# IPMC_MACP.net
KiCad netlist of a schematic drawn in Altium Designer
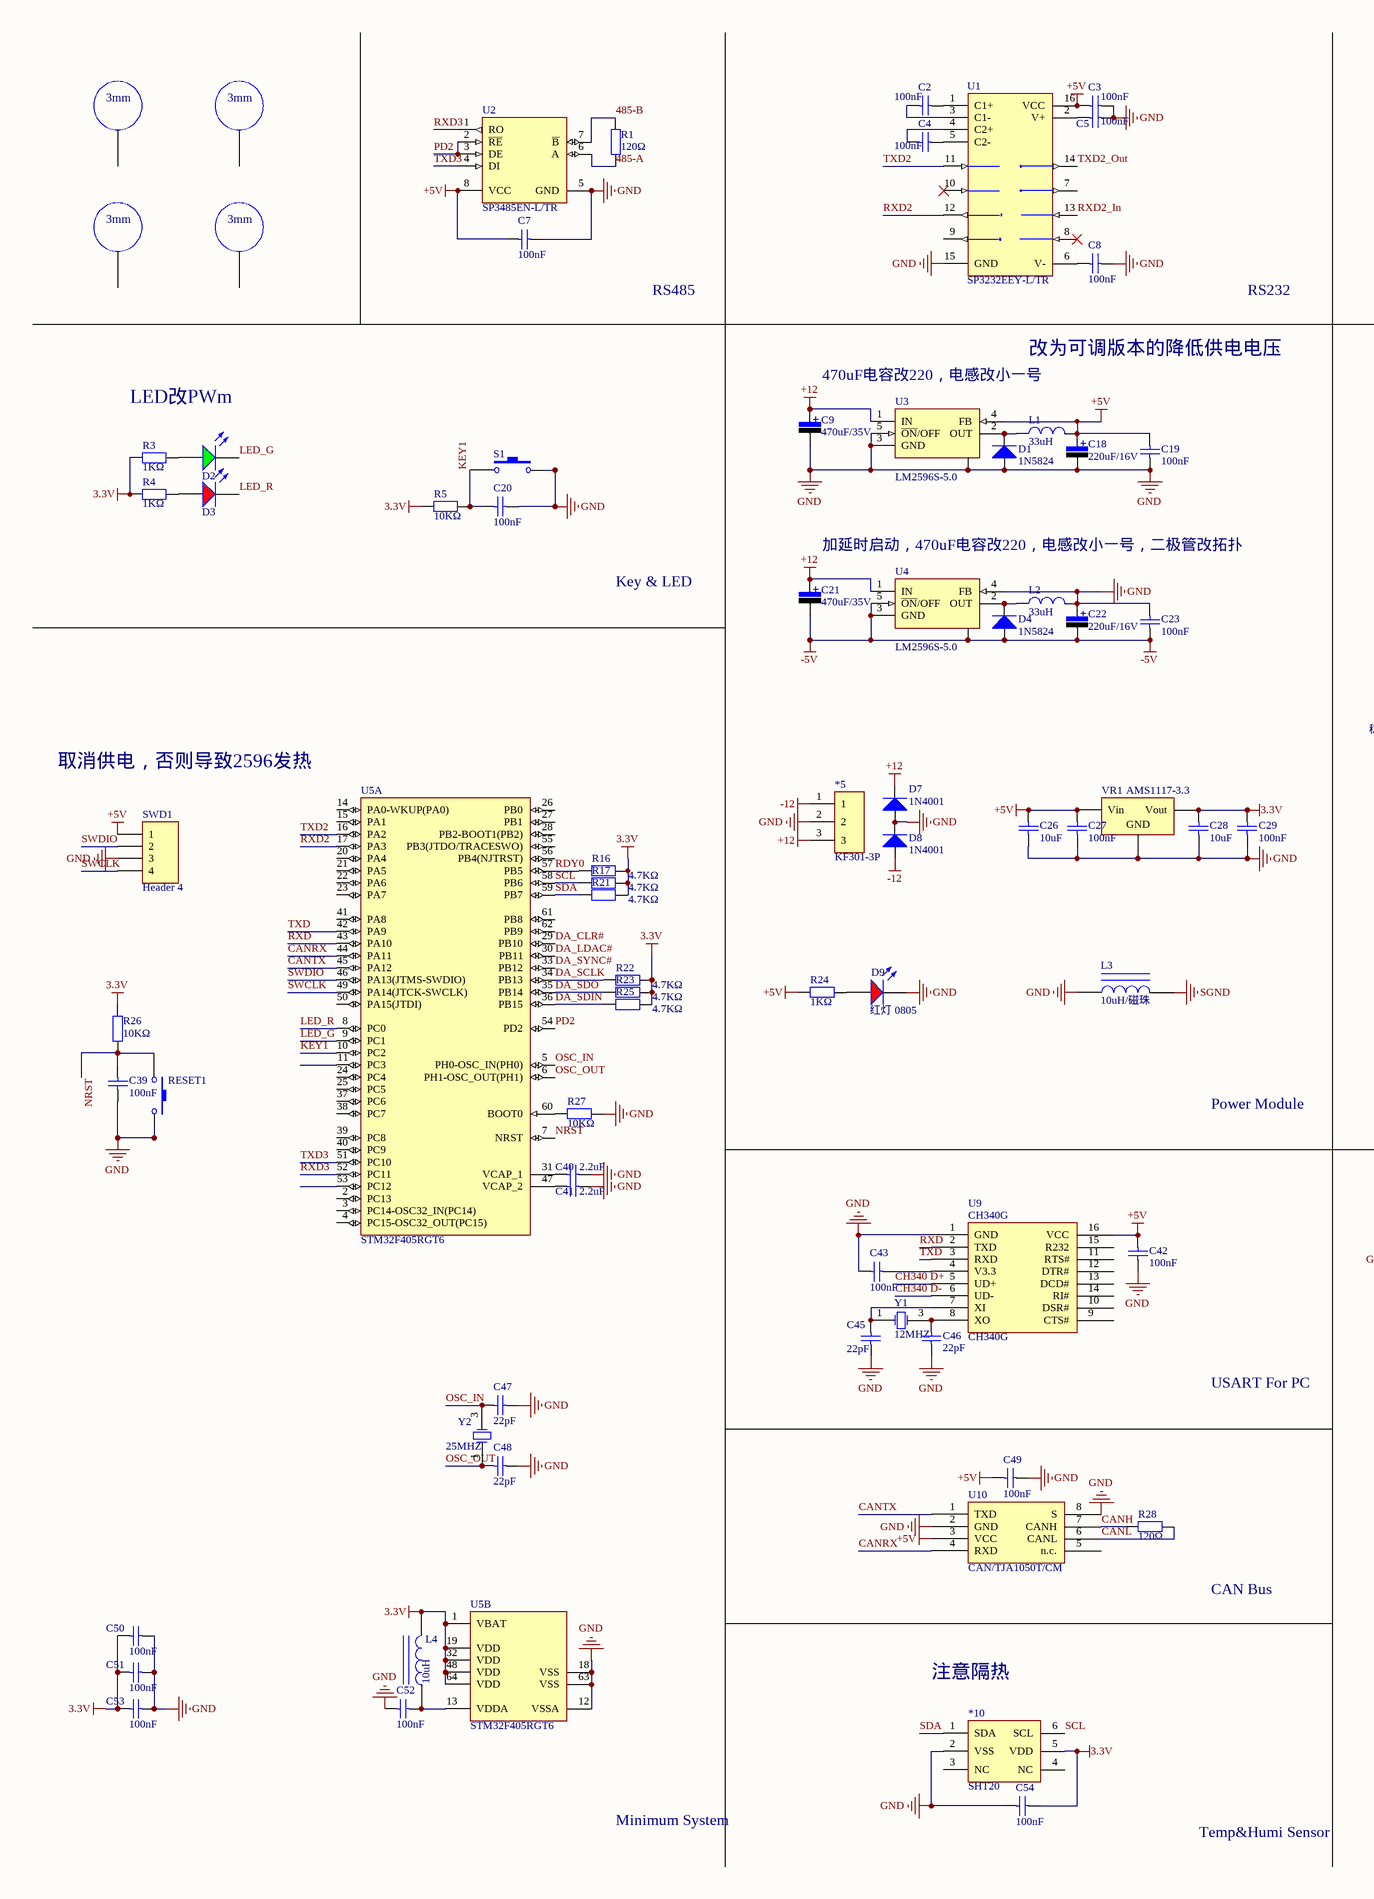
[diagram p0: IPMC_MACP.SchDoc, left]
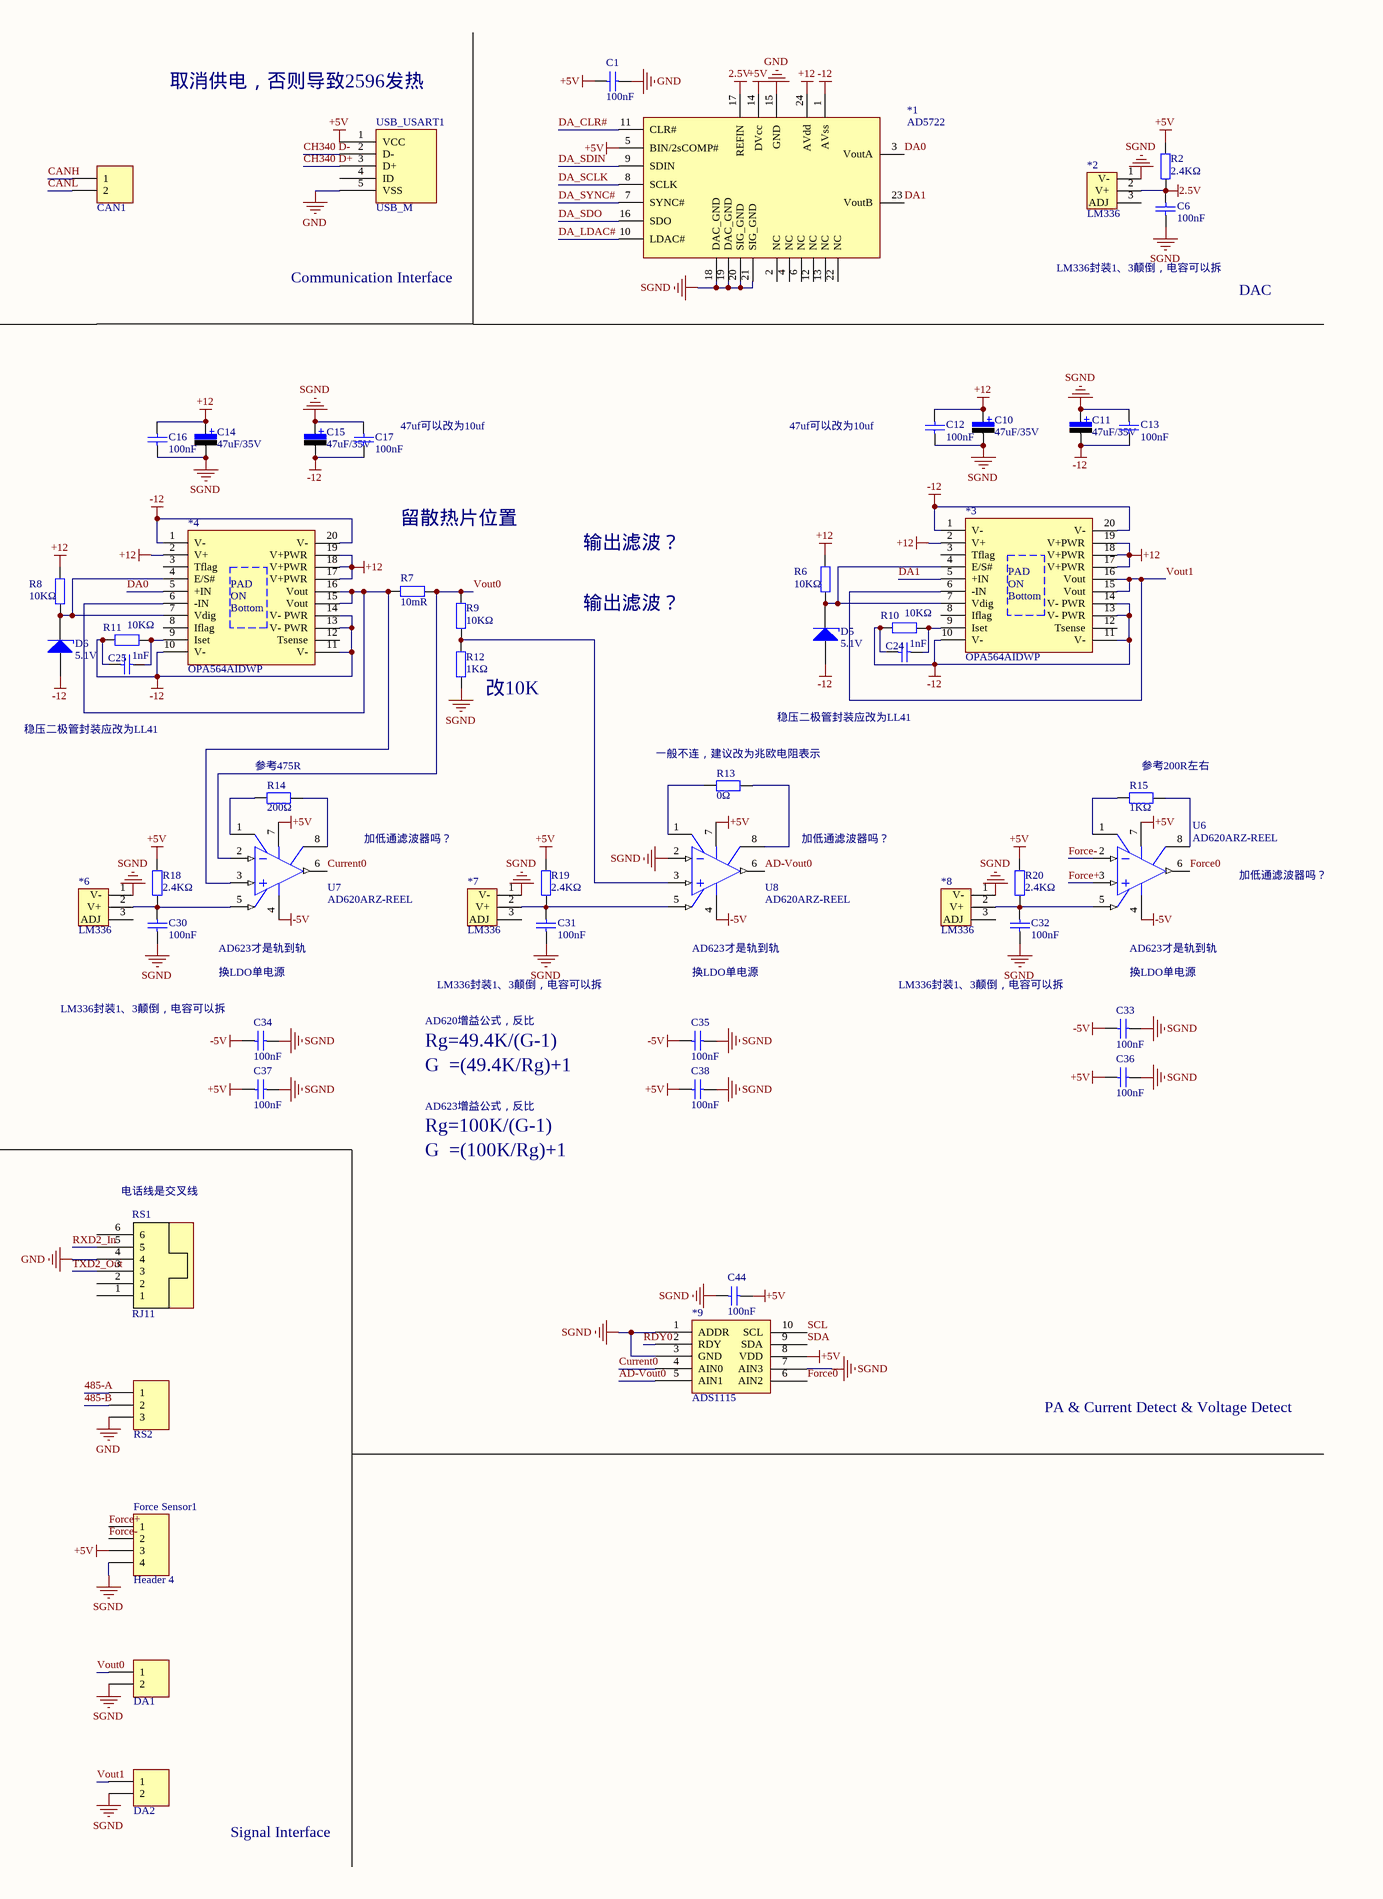
[diagram p1: IPMC_MACP.SchDoc, right]

(export (version "E")
  (design (tool "Eeschema 10.0.6"))
  (components
    (comp (ref "*1")
      (value "AD5722")
      (footprint "TSSOP24P")
      (description "双极性DAC")
      (libsource (lib "fszhang") (part "AD5722"))
    )
    (comp (ref "*2")
      (value "LM336")
      (footprint "TO-92A")
      (description "基准电压芯片2.5/5V")
      (libsource (lib "fszhang") (part "LM336"))
    )
    (comp (ref "*3")
      (value "OPA564AIDWP")
      (footprint "HSOP20")
      (description "PAD on Bottom")
      (libsource (lib "fszhang") (part "OPA564AIDWP"))
    )
    (comp (ref "*4")
      (value "OPA564AIDWP")
      (footprint "HSOP20")
      (description "PAD on Bottom")
      (libsource (lib "fszhang") (part "OPA564AIDWP"))
    )
    (comp (ref "*5")
      (value "KF301-3P")
      (footprint "KF301-3P")
      (description "蓝色端子")
      (libsource (lib "fszhang") (part "KF301-3P"))
    )
    (comp (ref "*6")
      (value "LM336")
      (footprint "TO-92A")
      (description "基准电压芯片2.5/5V")
      (libsource (lib "fszhang") (part "LM336"))
    )
    (comp (ref "*7")
      (value "LM336")
      (footprint "TO-92A")
      (description "基准电压芯片2.5/5V")
      (libsource (lib "fszhang") (part "LM336"))
    )
    (comp (ref "*8")
      (value "LM336")
      (footprint "TO-92A")
      (description "基准电压芯片2.5/5V")
      (libsource (lib "fszhang") (part "LM336"))
    )
    (comp (ref "*9") (value "ADS1115") (footprint "MSOP-UN10_N") (libsource (lib "fszhang") (part "ADS1115")))
    (comp (ref "*10") (value "SHT20") (footprint "DFN6") (libsource (lib "fszhang") (part "SHT20")))
    (comp (ref "C1")
      (value "100nF")
      (footprint "0805_C")
      (description "贴片电容")
      (libsource (lib "Miscellaneous Devices LC") (part "0805 100nF(104) 10% 50V"))
    )
    (comp (ref "C2")
      (value "100nF")
      (footprint "0805_C")
      (description "贴片电容")
      (libsource (lib "Miscellaneous Devices LC") (part "0805 100nF(104) 10% 50V"))
    )
    (comp (ref "C3")
      (value "100nF")
      (footprint "0805_C")
      (description "贴片电容")
      (libsource (lib "Miscellaneous Devices LC") (part "0805 100nF(104) 10% 50V"))
    )
    (comp (ref "C4")
      (value "100nF")
      (footprint "0805_C")
      (description "贴片电容")
      (libsource (lib "Miscellaneous Devices LC") (part "0805 100nF(104) 10% 50V"))
    )
    (comp (ref "C5")
      (value "100nF")
      (footprint "0805_C")
      (description "贴片电容")
      (libsource (lib "Miscellaneous Devices LC") (part "0805 100nF(104) 10% 50V"))
    )
    (comp (ref "C6")
      (value "100nF")
      (footprint "0805_C")
      (description "贴片电容")
      (libsource (lib "Miscellaneous Devices LC") (part "0805 100nF(104) 10% 50V"))
    )
    (comp (ref "C7")
      (value "100nF")
      (footprint "0805_C")
      (description "贴片电容")
      (libsource (lib "Miscellaneous Devices LC") (part "0805 100nF(104) 10% 50V"))
    )
    (comp (ref "C8")
      (value "100nF")
      (footprint "0805_C")
      (description "贴片电容")
      (libsource (lib "Miscellaneous Devices LC") (part "0805 100nF(104) 10% 50V"))
    )
    (comp (ref "C9")
      (value "470uF/35V")
      (footprint "C-RB-S10")
      (description "极性电解电容")
      (fields (field (name "PUBLISHER") "Altium Limited"))
      (libsource (lib "fszhang") (part "Cap Pol"))
    )
    (comp (ref "C10")
      (value "47uF/35V")
      (footprint "C-RB-S6")
      (description "极性电解电容")
      (fields (field (name "PUBLISHER") "Altium Limited"))
      (libsource (lib "fszhang") (part "Cap Pol"))
    )
    (comp (ref "C11")
      (value "47uF/35V")
      (footprint "C-RB-S6")
      (description "极性电解电容")
      (fields (field (name "PUBLISHER") "Altium Limited"))
      (libsource (lib "fszhang") (part "Cap Pol"))
    )
    (comp (ref "C12")
      (value "100nF")
      (footprint "0805_C")
      (description "贴片电容")
      (libsource (lib "Miscellaneous Devices LC") (part "0805 100nF(104) 10% 50V"))
    )
    (comp (ref "C13")
      (value "100nF")
      (footprint "0805_C")
      (description "贴片电容")
      (libsource (lib "Miscellaneous Devices LC") (part "0805 100nF(104) 10% 50V"))
    )
    (comp (ref "C14")
      (value "47uF/35V")
      (footprint "C-RB-S6")
      (description "极性电解电容")
      (fields (field (name "PUBLISHER") "Altium Limited"))
      (libsource (lib "fszhang") (part "Cap Pol"))
    )
    (comp (ref "C15")
      (value "47uF/35V")
      (footprint "C-RB-S6")
      (description "极性电解电容")
      (fields (field (name "PUBLISHER") "Altium Limited"))
      (libsource (lib "fszhang") (part "Cap Pol"))
    )
    (comp (ref "C16")
      (value "100nF")
      (footprint "0805_C")
      (description "贴片电容")
      (libsource (lib "Miscellaneous Devices LC") (part "0805 100nF(104) 10% 50V"))
    )
    (comp (ref "C17")
      (value "100nF")
      (footprint "0805_C")
      (description "贴片电容")
      (libsource (lib "Miscellaneous Devices LC") (part "0805 100nF(104) 10% 50V"))
    )
    (comp (ref "C18")
      (value "220uF/16V")
      (footprint "C-RB-S6")
      (description "极性电解电容")
      (fields (field (name "PUBLISHER") "Altium Limited"))
      (libsource (lib "fszhang") (part "Cap Pol"))
    )
    (comp (ref "C19")
      (value "100nF")
      (footprint "0805_C")
      (description "贴片电容")
      (libsource (lib "Miscellaneous Devices LC") (part "0805 100nF(104) 10% 50V"))
    )
    (comp (ref "C20")
      (value "100nF")
      (footprint "0805_C")
      (description "贴片电容")
      (libsource (lib "Miscellaneous Devices LC") (part "0805 100nF(104) 10% 50V"))
    )
    (comp (ref "C21")
      (value "470uF/35V")
      (footprint "C-RB-S10")
      (description "极性电解电容")
      (fields (field (name "PUBLISHER") "Altium Limited"))
      (libsource (lib "fszhang") (part "Cap Pol"))
    )
    (comp (ref "C22")
      (value "220uF/16V")
      (footprint "C-RB-S6")
      (description "极性电解电容")
      (fields (field (name "PUBLISHER") "Altium Limited"))
      (libsource (lib "fszhang") (part "Cap Pol"))
    )
    (comp (ref "C23")
      (value "100nF")
      (footprint "0805_C")
      (description "贴片电容")
      (libsource (lib "Miscellaneous Devices LC") (part "0805 100nF(104) 10% 50V"))
    )
    (comp (ref "C24")
      (value "1nF")
      (footprint "0805_C")
      (description "贴片电容")
      (libsource (lib "Miscellaneous Devices LC") (part "0805 1nF (102) 10% 50V"))
    )
    (comp (ref "C25")
      (value "1nF")
      (footprint "0805_C")
      (description "贴片电容")
      (libsource (lib "Miscellaneous Devices LC") (part "0805 1nF (102) 10% 50V"))
    )
    (comp (ref "C26")
      (value "10uF")
      (footprint "0805_C")
      (description "贴片电容")
      (libsource (lib "Miscellaneous Devices LC") (part "0805 10uF (106) 10% 25V"))
    )
    (comp (ref "C27")
      (value "100nF")
      (footprint "0805_C")
      (description "贴片电容")
      (libsource (lib "Miscellaneous Devices LC") (part "0805 100nF(104) 10% 50V"))
    )
    (comp (ref "C28")
      (value "10uF")
      (footprint "0805_C")
      (description "贴片电容")
      (libsource (lib "Miscellaneous Devices LC") (part "0805 10uF (106) 10% 25V"))
    )
    (comp (ref "C29")
      (value "100nF")
      (footprint "0805_C")
      (description "贴片电容")
      (libsource (lib "Miscellaneous Devices LC") (part "0805 100nF(104) 10% 50V"))
    )
    (comp (ref "C30")
      (value "100nF")
      (footprint "0805_C")
      (description "贴片电容")
      (libsource (lib "Miscellaneous Devices LC") (part "0805 100nF(104) 10% 50V"))
    )
    (comp (ref "C31")
      (value "100nF")
      (footprint "0805_C")
      (description "贴片电容")
      (libsource (lib "Miscellaneous Devices LC") (part "0805 100nF(104) 10% 50V"))
    )
    (comp (ref "C32")
      (value "100nF")
      (footprint "0805_C")
      (description "贴片电容")
      (libsource (lib "Miscellaneous Devices LC") (part "0805 100nF(104) 10% 50V"))
    )
    (comp (ref "C33")
      (value "100nF")
      (footprint "0805_C")
      (description "贴片电容")
      (libsource (lib "Miscellaneous Devices LC") (part "0805 100nF(104) 10% 50V"))
    )
    (comp (ref "C34")
      (value "100nF")
      (footprint "0805_C")
      (description "贴片电容")
      (libsource (lib "Miscellaneous Devices LC") (part "0805 100nF(104) 10% 50V"))
    )
    (comp (ref "C35")
      (value "100nF")
      (footprint "0805_C")
      (description "贴片电容")
      (libsource (lib "Miscellaneous Devices LC") (part "0805 100nF(104) 10% 50V"))
    )
    (comp (ref "C36")
      (value "100nF")
      (footprint "0805_C")
      (description "贴片电容")
      (libsource (lib "Miscellaneous Devices LC") (part "0805 100nF(104) 10% 50V"))
    )
    (comp (ref "C37")
      (value "100nF")
      (footprint "0805_C")
      (description "贴片电容")
      (libsource (lib "Miscellaneous Devices LC") (part "0805 100nF(104) 10% 50V"))
    )
    (comp (ref "C38")
      (value "100nF")
      (footprint "0805_C")
      (description "贴片电容")
      (libsource (lib "Miscellaneous Devices LC") (part "0805 100nF(104) 10% 50V"))
    )
    (comp (ref "C39")
      (value "100nF")
      (footprint "0805_C")
      (description "贴片电容")
      (libsource (lib "Miscellaneous Devices LC") (part "0805 100nF(104) 10% 50V"))
    )
    (comp (ref "C40")
      (value "2.2uF")
      (footprint "0805_C")
      (description "贴片电容")
      (libsource (lib "Miscellaneous Devices LC") (part "0805 2.2uF (225) 20% 50V"))
    )
    (comp (ref "C41")
      (value "2.2uF")
      (footprint "0805_C")
      (description "贴片电容")
      (libsource (lib "Miscellaneous Devices LC") (part "0805 2.2uF (225) 20% 50V"))
    )
    (comp (ref "C42")
      (value "100nF")
      (footprint "0805_C")
      (description "贴片电容")
      (libsource (lib "Miscellaneous Devices LC") (part "0805 100nF(104) 10% 50V"))
    )
    (comp (ref "C43")
      (value "100nF")
      (footprint "0805_C")
      (description "贴片电容")
      (libsource (lib "Miscellaneous Devices LC") (part "0805 100nF(104) 10% 50V"))
    )
    (comp (ref "C44")
      (value "100nF")
      (footprint "0805_C")
      (description "贴片电容")
      (libsource (lib "Miscellaneous Devices LC") (part "0805 100nF(104) 10% 50V"))
    )
    (comp (ref "C45")
      (value "22pF")
      (footprint "0805_C")
      (description "贴片电容")
      (libsource (lib "Miscellaneous Devices LC") (part "0805 22pF (220) 5% 50V"))
    )
    (comp (ref "C46")
      (value "22pF")
      (footprint "0805_C")
      (description "贴片电容")
      (libsource (lib "Miscellaneous Devices LC") (part "0805 22pF (220) 5% 50V"))
    )
    (comp (ref "C47")
      (value "22pF")
      (footprint "0805_C")
      (description "贴片电容")
      (libsource (lib "Miscellaneous Devices LC") (part "0805 22pF (220) 5% 50V"))
    )
    (comp (ref "C48")
      (value "22pF")
      (footprint "0805_C")
      (description "贴片电容")
      (libsource (lib "Miscellaneous Devices LC") (part "0805 22pF (220) 5% 50V"))
    )
    (comp (ref "C49")
      (value "100nF")
      (footprint "0805_C")
      (description "贴片电容")
      (libsource (lib "Miscellaneous Devices LC") (part "0805 100nF(104) 10% 50V"))
    )
    (comp (ref "C50")
      (value "100nF")
      (footprint "0805_C")
      (description "贴片电容")
      (libsource (lib "Miscellaneous Devices LC") (part "0805 100nF(104) 10% 50V"))
    )
    (comp (ref "C51")
      (value "100nF")
      (footprint "0805_C")
      (description "贴片电容")
      (libsource (lib "Miscellaneous Devices LC") (part "0805 100nF(104) 10% 50V"))
    )
    (comp (ref "C52")
      (value "100nF")
      (footprint "0805_C")
      (description "贴片电容")
      (libsource (lib "Miscellaneous Devices LC") (part "0805 100nF(104) 10% 50V"))
    )
    (comp (ref "C53")
      (value "100nF")
      (footprint "0805_C")
      (description "贴片电容")
      (libsource (lib "Miscellaneous Devices LC") (part "0805 100nF(104) 10% 50V"))
    )
    (comp (ref "C54")
      (value "100nF")
      (footprint "0805_C")
      (description "贴片电容")
      (libsource (lib "Miscellaneous Devices LC") (part "0805 100nF(104) 10% 50V"))
    )
    (comp (ref "CAN1")
      (value "Header 2")
      (footprint "HDR2X1_B1")
      (description "接插件")
      (fields (field (name "PUBLISHER") "Altium Limited"))
      (libsource (lib "fszhang") (part "Header 2"))
    )
    (comp (ref "D1")
      (value "1N5824")
      (footprint "DIODE-SMA")
      (description "二极管")
      (fields (field (name "PUBLISHER") "Altium Limited"))
      (libsource (lib "fszhang") (part "Diode"))
    )
    (comp (ref "D2")
      (value "翠绿 0805")
      (footprint "0805_LED_S1")
      (description "发光二极管")
      (libsource (lib "Miscellaneous Devices LC") (part "0805 翠绿"))
    )
    (comp (ref "D3")
      (value "红灯 0805")
      (footprint "0805_LED_S1")
      (description "发光二极管")
      (libsource (lib "Miscellaneous Devices LC") (part "0805 红灯"))
    )
    (comp (ref "D4")
      (value "1N5824")
      (footprint "DIODE-SMA")
      (description "二极管")
      (fields (field (name "PUBLISHER") "Altium Limited"))
      (libsource (lib "fszhang") (part "Diode"))
    )
    (comp (ref "D5")
      (value "5.1V")
      (footprint "DIODE-1206")
      (description "稳压二极管")
      (fields (field (name "PUBLISHER") "Altium Limited"))
      (libsource (lib "fszhang") (part "Diode-Z"))
    )
    (comp (ref "D6")
      (value "5.1V")
      (footprint "DIODE-1206")
      (description "稳压二极管")
      (fields (field (name "PUBLISHER") "Altium Limited"))
      (libsource (lib "fszhang") (part "Diode-Z"))
    )
    (comp (ref "D7")
      (value "1N4001")
      (footprint "DIODE-SMA")
      (description "二极管")
      (fields (field (name "PUBLISHER") "Altium Limited"))
      (libsource (lib "fszhang") (part "Diode"))
    )
    (comp (ref "D8")
      (value "1N4001")
      (footprint "DIODE-SMA")
      (description "二极管")
      (fields (field (name "PUBLISHER") "Altium Limited"))
      (libsource (lib "fszhang") (part "Diode"))
    )
    (comp (ref "D9")
      (value "红灯 0805")
      (footprint "0805_LED_S1")
      (description "发光二极管")
      (libsource (lib "Miscellaneous Devices LC") (part "0805 红灯"))
    )
    (comp (ref "DA1")
      (value "Header 2")
      (footprint "HDR2X1_B1")
      (description "接插件")
      (fields (field (name "PUBLISHER") "Altium Limited"))
      (libsource (lib "fszhang") (part "Header 2"))
    )
    (comp (ref "DA2")
      (value "Header 2")
      (footprint "HDR2X1_B1")
      (description "接插件")
      (fields (field (name "PUBLISHER") "Altium Limited"))
      (libsource (lib "fszhang") (part "Header 2"))
    )
    (comp (ref "Force Sensor1")
      (value "Header 4")
      (footprint "fszhang:HDR4X1_B1")
      (description "Header, 4-Pin")
      (fields (field (name "PUBLISHER") "Altium Limited"))
      (libsource (lib "Miscellaneous Connectors") (part "Header 4"))
    )
    (comp (ref "L1")
      (value "33uH")
      (footprint "L-SMD-12")
      (description "电感")
      (fields (field (name "PUBLISHER") "Altium Limited"))
      (libsource (lib "fszhang") (part "Inductor"))
    )
    (comp (ref "L2")
      (value "33uH")
      (footprint "L-SMD-12")
      (description "电感")
      (fields (field (name "PUBLISHER") "Altium Limited"))
      (libsource (lib "fszhang") (part "Inductor"))
    )
    (comp (ref "L3")
      (value "10uH/磁珠")
      (footprint "0805_L")
      (description "贴片电感")
      (libsource (lib "Miscellaneous Devices LC") (part "0805 10uH 10%"))
    )
    (comp (ref "L4")
      (value "10uH")
      (footprint "0805_L")
      (description "贴片电感")
      (libsource (lib "Miscellaneous Devices LC") (part "0805 10uH 10%"))
    )
    (comp (ref "R1")
      (value "120Ω")
      (footprint "0805_R")
      (description "贴片电阻")
      (libsource (lib "") (part "0805 120Ω (1200) 1%_1"))
    )
    (comp (ref "R2")
      (value "2.4KΩ")
      (footprint "0805_R")
      (description "贴片电阻")
      (libsource (lib "Miscellaneous Devices LC") (part "0805 2.4KΩ (2401) 1%"))
    )
    (comp (ref "R3")
      (value "1KΩ")
      (footprint "0805_R")
      (description "贴片电阻")
      (libsource (lib "Miscellaneous Devices LC") (part "0805 1KΩ (1001) 1%"))
    )
    (comp (ref "R4")
      (value "1KΩ")
      (footprint "0805_R")
      (description "贴片电阻")
      (libsource (lib "Miscellaneous Devices LC") (part "0805 1KΩ (1001) 1%"))
    )
    (comp (ref "R5")
      (value "10KΩ")
      (footprint "0805_R")
      (description "贴片电阻")
      (libsource (lib "") (part "0805 10KΩ (1002) 1%_1"))
    )
    (comp (ref "R6")
      (value "10KΩ")
      (footprint "0805_R")
      (description "贴片电阻")
      (libsource (lib "Miscellaneous Devices LC") (part "0805 10KΩ (1002) 1%"))
    )
    (comp (ref "R7")
      (value "10mR")
      (footprint "2512")
      (description "贴片电阻")
      (fields (field (name "PUBLISHER") "Altium Limited"))
      (libsource (lib "fszhang") (part "Res1"))
    )
    (comp (ref "R8")
      (value "10KΩ")
      (footprint "0805_R")
      (description "贴片电阻")
      (libsource (lib "Miscellaneous Devices LC") (part "0805 10KΩ (1002) 1%"))
    )
    (comp (ref "R9")
      (value "10KΩ")
      (footprint "0805_R")
      (description "贴片电阻")
      (libsource (lib "Miscellaneous Devices LC") (part "0805 20KΩ (2002) 1%"))
    )
    (comp (ref "R10")
      (value "10KΩ")
      (footprint "0805_R")
      (description "贴片电阻")
      (libsource (lib "") (part "0805 10KΩ (1002) 1%_1"))
    )
    (comp (ref "R11")
      (value "10KΩ")
      (footprint "0805_R")
      (description "贴片电阻")
      (libsource (lib "") (part "0805 10KΩ (1002) 1%_1"))
    )
    (comp (ref "R12")
      (value "1KΩ")
      (footprint "0805_R")
      (description "贴片电阻")
      (libsource (lib "Miscellaneous Devices LC") (part "0805 20KΩ (2002) 1%"))
    )
    (comp (ref "R13")
      (value "0Ω")
      (footprint "0805_R")
      (description "贴片电阻")
      (libsource (lib "Miscellaneous Devices LC") (part "0805 0Ω (0R0) 1%"))
    )
    (comp (ref "R14")
      (value "200Ω")
      (footprint "0805_R")
      (description "贴片电阻")
      (libsource (lib "Miscellaneous Devices LC") (part "0805 200Ω (2000) 1%"))
    )
    (comp (ref "R15")
      (value "1KΩ")
      (footprint "0805_R")
      (description "贴片电阻")
      (libsource (lib "Miscellaneous Devices LC") (part "0805 1KΩ (1001) 1%"))
    )
    (comp (ref "R16")
      (value "4.7KΩ")
      (footprint "0805_R")
      (description "贴片电阻")
      (libsource (lib "Miscellaneous Devices LC") (part "0805 4.7KΩ (4701) 1%"))
    )
    (comp (ref "R17")
      (value "4.7KΩ")
      (footprint "0805_R")
      (description "贴片电阻")
      (libsource (lib "Miscellaneous Devices LC") (part "0805 4.7KΩ (4701) 1%"))
    )
    (comp (ref "R18")
      (value "2.4KΩ")
      (footprint "0805_R")
      (description "贴片电阻")
      (libsource (lib "Miscellaneous Devices LC") (part "0805 2.4KΩ (2401) 1%"))
    )
    (comp (ref "R19")
      (value "2.4KΩ")
      (footprint "0805_R")
      (description "贴片电阻")
      (libsource (lib "Miscellaneous Devices LC") (part "0805 2.4KΩ (2401) 1%"))
    )
    (comp (ref "R20")
      (value "2.4KΩ")
      (footprint "0805_R")
      (description "贴片电阻")
      (libsource (lib "Miscellaneous Devices LC") (part "0805 2.4KΩ (2401) 1%"))
    )
    (comp (ref "R21")
      (value "4.7KΩ")
      (footprint "0805_R")
      (description "贴片电阻")
      (libsource (lib "Miscellaneous Devices LC") (part "0805 4.7KΩ (4701) 1%"))
    )
    (comp (ref "R22")
      (value "4.7KΩ")
      (footprint "0805_R")
      (description "贴片电阻")
      (libsource (lib "Miscellaneous Devices LC") (part "0805 4.7KΩ (4701) 1%"))
    )
    (comp (ref "R23")
      (value "4.7KΩ")
      (footprint "0805_R")
      (description "贴片电阻")
      (libsource (lib "Miscellaneous Devices LC") (part "0805 4.7KΩ (4701) 1%"))
    )
    (comp (ref "R24")
      (value "1KΩ")
      (footprint "0805_R")
      (description "贴片电阻")
      (libsource (lib "Miscellaneous Devices LC") (part "0805 1KΩ (1001) 1%"))
    )
    (comp (ref "R25")
      (value "4.7KΩ")
      (footprint "0805_R")
      (description "贴片电阻")
      (libsource (lib "Miscellaneous Devices LC") (part "0805 4.7KΩ (4701) 1%"))
    )
    (comp (ref "R26")
      (value "10KΩ")
      (footprint "0805_R")
      (description "贴片电阻")
      (libsource (lib "") (part "0805 10KΩ (1002) 1%_3"))
    )
    (comp (ref "R27")
      (value "10KΩ")
      (footprint "0805_R")
      (description "贴片电阻")
      (libsource (lib "") (part "0805 10KΩ (1002) 1%_2"))
    )
    (comp (ref "R28")
      (value "120Ω")
      (footprint "0805_R")
      (description "贴片电阻")
      (libsource (lib "Miscellaneous Devices LC") (part "0805 120Ω (1200) 1%"))
    )
    (comp (ref "RESET1")
      (value "SW-PB")
      (footprint "SW_PB2_A1")
      (description "微动开关")
      (fields (field (name "PUBLISHER") "Altium Limited"))
      (libsource (lib "fszhang") (part "SW-PB"))
    )
    (comp (ref "RS1") (value "RJ11") (footprint "RJ6-RJ11") (libsource (lib "fszhang") (part "RJ11")))
    (comp (ref "RS2")
      (value "Header 3")
      (footprint "HDR3X1_B1")
      (description "接插件")
      (fields (field (name "PUBLISHER") "Altium Limited"))
      (libsource (lib "fszhang") (part "Header 3"))
    )
    (comp (ref "S1")
      (value "SW-PB")
      (footprint "SW_PB2_A1")
      (description "微动开关")
      (fields (field (name "PUBLISHER") "Altium Limited"))
      (libsource (lib "fszhang") (part "SW-PB"))
    )
    (comp (ref "SWD1")
      (value "Header 4")
      (footprint "HDR1X4")
      (description "Header, 4-Pin")
      (fields (field (name "PUBLISHER") "Altium Limited"))
      (libsource (lib "Miscellaneous Connectors") (part "Header 4"))
    )
    (comp (ref "T1") (value "M3铜柱螺丝孔") (footprint "螺丝孔-3mm") (libsource (lib "fszhang") (part "M3铜柱螺丝孔")))
    (comp (ref "T2") (value "M3铜柱螺丝孔") (footprint "螺丝孔-3mm") (libsource (lib "fszhang") (part "M3铜柱螺丝孔")))
    (comp (ref "T3") (value "M3铜柱螺丝孔") (footprint "螺丝孔-3mm") (libsource (lib "fszhang") (part "M3铜柱螺丝孔")))
    (comp (ref "T4") (value "M3铜柱螺丝孔") (footprint "螺丝孔-3mm") (libsource (lib "fszhang") (part "M3铜柱螺丝孔")))
    (comp (ref "U1")
      (value "SP3232EEY-L/TR")
      (footprint "TSSOP-16")
      (description "RS232")
      (libsource (lib "Miscellaneous Devices LC") (part "SP3232EEY-L/TR"))
    )
    (comp (ref "U2")
      (value "SP3485EN-L/TR")
      (footprint "SOIC-8_150mil")
      (description "RS-485/RS-422")
      (libsource (lib "Miscellaneous Devices LC") (part "SP3485EN-L/TR"))
    )
    (comp (ref "U3")
      (value "LM2596S-5.0")
      (footprint "TO-263-5")
      (description "5V稳压芯片")
      (fields (field (name "PUBLISHER") "Altium Limited"))
      (libsource (lib "fszhang") (part "LM2596S-5.0"))
    )
    (comp (ref "U4")
      (value "LM2596S-5.0")
      (footprint "TO-263-5")
      (description "5V稳压芯片")
      (fields (field (name "PUBLISHER") "Altium Limited"))
      (libsource (lib "fszhang") (part "LM2596S-5.0"))
    )
    (comp (ref "U5")
      (value "STM32F405RGT6")
      (footprint "STM-LQFP64_L")
      (fields (field (name "MANUFACTURER") "STMicroelectronics"))
      (libsource (lib "STMicroelectronics STM32 F4") (part "STM32F405RGT6"))
    )
    (comp (ref "U6")
      (value "AD620ARZ-REEL")
      (footprint "SOIC-8_150mil")
      (description "仪放")
      (libsource (lib "Miscellaneous Devices LC") (part "AD620ARZ-REEL"))
    )
    (comp (ref "U7")
      (value "AD620ARZ-REEL")
      (footprint "SOIC-8_150mil")
      (description "仪放")
      (libsource (lib "Miscellaneous Devices LC") (part "AD620ARZ-REEL"))
    )
    (comp (ref "U8")
      (value "AD620ARZ-REEL")
      (footprint "SOIC-8_150mil")
      (description "仪放")
      (libsource (lib "Miscellaneous Devices LC") (part "AD620ARZ-REEL"))
    )
    (comp (ref "U9")
      (value "CH340G")
      (footprint "SOIC-16_150mil")
      (description "USB")
      (libsource (lib "Miscellaneous Devices LC") (part "CH340G"))
    )
    (comp (ref "U10")
      (value "CAN/TJA1050T/CM")
      (footprint "SOIC-8_150mil")
      (description "CAN")
      (libsource (lib "Miscellaneous Devices LC") (part "CAN/TJA1050T/CM"))
    )
    (comp (ref "USB_USART1")
      (value "USB_M")
      (footprint "USB_MICRO")
      (description "MicroUSB接口")
      (libsource (lib "fszhang") (part "USB_M"))
    )
    (comp (ref "VR1")
      (value "AMS1117-3.3")
      (footprint "SOT-223")
      (description "低压差线性稳压(LDO)")
      (libsource (lib "Miscellaneous Devices LC") (part "SOT-223 AMS1117-3.3"))
    )
    (comp (ref "Y1")
      (value "12MHZ")
      (footprint "SMD-3225_4P")
      (description "贴片晶振")
      (libsource (lib "Miscellaneous Devices LC") (part "SMD-3225_4P  12MHZ 20PF 10PPM"))
    )
    (comp (ref "Y2")
      (value "25MHZ")
      (footprint "SMD-3225_4P")
      (description "贴片晶振")
      (libsource (lib "Miscellaneous Devices LC") (part "SMD-3225_4P  25MHZ 12PF 10PPM"))
    )
  )
  (nets
    (net (code "1") (name "+5V") (class "Default")
      (node (ref "*1") (pin "14") (pinfunction "DVcc_14") (pintype "passive"))
      (node (ref "*1") (pin "5") (pinfunction "BIN/2sCOMP#_5") (pintype "passive"))
      (node (ref "*9") (pin "8") (pinfunction "VDD_8") (pintype "passive"))
      (node (ref "C1") (pin "2") (pinfunction "2_2") (pintype "passive"))
      (node (ref "C18") (pin "1") (pinfunction "1_1") (pintype "passive"))
      (node (ref "C19") (pin "2") (pinfunction "2_2") (pintype "passive"))
      (node (ref "C26") (pin "2") (pinfunction "2_2") (pintype "passive"))
      (node (ref "C27") (pin "2") (pinfunction "2_2") (pintype "passive"))
      (node (ref "C3") (pin "1") (pinfunction "1_1") (pintype "passive"))
      (node (ref "C36") (pin "2") (pinfunction "2_2") (pintype "passive"))
      (node (ref "C37") (pin "2") (pinfunction "2_2") (pintype "passive"))
      (node (ref "C38") (pin "2") (pinfunction "2_2") (pintype "passive"))
      (node (ref "C42") (pin "2") (pinfunction "2_2") (pintype "passive"))
      (node (ref "C44") (pin "1") (pinfunction "1_1") (pintype "passive"))
      (node (ref "C49") (pin "2") (pinfunction "2_2") (pintype "passive"))
      (node (ref "C7") (pin "2") (pinfunction "2_2") (pintype "passive"))
      (node (ref "Force Sensor1") (pin "3") (pinfunction "3_3") (pintype "passive"))
      (node (ref "L1") (pin "2") (pinfunction "2_2") (pintype "passive"))
      (node (ref "R18") (pin "2") (pinfunction "2_2") (pintype "passive"))
      (node (ref "R19") (pin "2") (pinfunction "2_2") (pintype "passive"))
      (node (ref "R2") (pin "2") (pinfunction "2_2") (pintype "passive"))
      (node (ref "R20") (pin "2") (pinfunction "2_2") (pintype "passive"))
      (node (ref "R24") (pin "1") (pinfunction "1_1") (pintype "passive"))
      (node (ref "SWD1") (pin "1") (pinfunction "1_1") (pintype "passive"))
      (node (ref "U1") (pin "16") (pinfunction "VCC_16") (pintype "power_in"))
      (node (ref "U10") (pin "3") (pinfunction "VCC_3") (pintype "passive"))
      (node (ref "U2") (pin "8") (pinfunction "VCC_8") (pintype "power_in"))
      (node (ref "U3") (pin "4") (pinfunction "FB_4") (pintype "input"))
      (node (ref "U6") (pin "7") (pinfunction "V+_7") (pintype "power_in"))
      (node (ref "U7") (pin "7") (pinfunction "V+_7") (pintype "power_in"))
      (node (ref "U8") (pin "7") (pinfunction "V+_7") (pintype "power_in"))
      (node (ref "U9") (pin "16") (pinfunction "VCC_16") (pintype "passive"))
      (node (ref "USB_USART1") (pin "1") (pinfunction "VCC_1") (pintype "passive"))
      (node (ref "VR1") (pin "3") (pinfunction "Vin_3") (pintype "passive"))
    )
    (net (code "2") (name "+12") (class "Default")
      (node (ref "*1") (pin "24") (pinfunction "AVdd_24") (pintype "passive"))
      (node (ref "*3") (pin "17") (pinfunction "V+PWR_17") (pintype "passive"))
      (node (ref "*3") (pin "18") (pinfunction "V+PWR_18") (pintype "passive"))
      (node (ref "*3") (pin "19") (pinfunction "V+PWR_19") (pintype "passive"))
      (node (ref "*3") (pin "2") (pinfunction "V+_2") (pintype "passive"))
      (node (ref "*4") (pin "17") (pinfunction "V+PWR_17") (pintype "passive"))
      (node (ref "*4") (pin "18") (pinfunction "V+PWR_18") (pintype "passive"))
      (node (ref "*4") (pin "19") (pinfunction "V+PWR_19") (pintype "passive"))
      (node (ref "*4") (pin "2") (pinfunction "V+_2") (pintype "passive"))
      (node (ref "*5") (pin "3") (pinfunction "3_3") (pintype "passive"))
      (node (ref "C10") (pin "1") (pinfunction "1_1") (pintype "passive"))
      (node (ref "C12") (pin "2") (pinfunction "2_2") (pintype "passive"))
      (node (ref "C14") (pin "1") (pinfunction "1_1") (pintype "passive"))
      (node (ref "C16") (pin "2") (pinfunction "2_2") (pintype "passive"))
      (node (ref "C21") (pin "1") (pinfunction "1_1") (pintype "passive"))
      (node (ref "C9") (pin "1") (pinfunction "1_1") (pintype "passive"))
      (node (ref "D7") (pin "2") (pinfunction "K_2") (pintype "passive"))
      (node (ref "R6") (pin "2") (pinfunction "2_2") (pintype "passive"))
      (node (ref "R8") (pin "2") (pinfunction "2_2") (pintype "passive"))
      (node (ref "U3") (pin "1") (pinfunction "IN_1") (pintype "power_in"))
      (node (ref "U4") (pin "1") (pinfunction "IN_1") (pintype "power_in"))
    )
    (net (code "3") (name "-5V") (class "Default")
      (node (ref "C21") (pin "2") (pinfunction "2_2") (pintype "passive"))
      (node (ref "C22") (pin "2") (pinfunction "2_2") (pintype "passive"))
      (node (ref "C23") (pin "1") (pinfunction "1_1") (pintype "passive"))
      (node (ref "C33") (pin "2") (pinfunction "2_2") (pintype "passive"))
      (node (ref "C34") (pin "2") (pinfunction "2_2") (pintype "passive"))
      (node (ref "C35") (pin "2") (pinfunction "2_2") (pintype "passive"))
      (node (ref "D4") (pin "1") (pinfunction "A_1") (pintype "passive"))
      (node (ref "U4") (pin "3") (pinfunction "GND_3") (pintype "power_in"))
      (node (ref "U4") (pin "5") (pinfunction "~{ON}/OFF_5") (pintype "input"))
      (node (ref "U4") (pin "6") (pinfunction "6_6") (pintype "power_in"))
      (node (ref "U6") (pin "4") (pinfunction "V-_4") (pintype "power_in"))
      (node (ref "U7") (pin "4") (pinfunction "V-_4") (pintype "power_in"))
      (node (ref "U8") (pin "4") (pinfunction "V-_4") (pintype "power_in"))
    )
    (net (code "4") (name "-12") (class "Default")
      (node (ref "*1") (pin "1") (pinfunction "AVss_1") (pintype "passive"))
      (node (ref "*3") (pin "1") (pinfunction "V-_1") (pintype "passive"))
      (node (ref "*3") (pin "10") (pinfunction "V-_10") (pintype "passive"))
      (node (ref "*3") (pin "11") (pinfunction "V-_11") (pintype "passive"))
      (node (ref "*3") (pin "13") (pinfunction "V-_PWR_13") (pintype "passive"))
      (node (ref "*3") (pin "14") (pinfunction "V-_PWR_14") (pintype "passive"))
      (node (ref "*3") (pin "20") (pinfunction "V-_20") (pintype "passive"))
      (node (ref "*4") (pin "1") (pinfunction "V-_1") (pintype "passive"))
      (node (ref "*4") (pin "10") (pinfunction "V-_10") (pintype "passive"))
      (node (ref "*4") (pin "11") (pinfunction "V-_11") (pintype "passive"))
      (node (ref "*4") (pin "13") (pinfunction "V-_PWR_13") (pintype "passive"))
      (node (ref "*4") (pin "14") (pinfunction "V-_PWR_14") (pintype "passive"))
      (node (ref "*4") (pin "20") (pinfunction "V-_20") (pintype "passive"))
      (node (ref "*5") (pin "1") (pinfunction "1_1") (pintype "passive"))
      (node (ref "C11") (pin "2") (pinfunction "2_2") (pintype "passive"))
      (node (ref "C13") (pin "2") (pinfunction "2_2") (pintype "passive"))
      (node (ref "C15") (pin "2") (pinfunction "2_2") (pintype "passive"))
      (node (ref "C17") (pin "2") (pinfunction "2_2") (pintype "passive"))
      (node (ref "C24") (pin "1") (pinfunction "1_1") (pintype "passive"))
      (node (ref "C25") (pin "1") (pinfunction "1_1") (pintype "passive"))
      (node (ref "D5") (pin "1") (pinfunction "A_1") (pintype "passive"))
      (node (ref "D6") (pin "1") (pinfunction "A_1") (pintype "passive"))
      (node (ref "D8") (pin "1") (pinfunction "A_1") (pintype "passive"))
      (node (ref "R10") (pin "1") (pinfunction "1_1") (pintype "passive"))
      (node (ref "R11") (pin "1") (pinfunction "1_1") (pintype "passive"))
    )
    (net (code "5") (name "/485-A") (class "Default")
      (node (ref "R1") (pin "1") (pinfunction "1_1") (pintype "passive"))
      (node (ref "RS2") (pin "1") (pinfunction "1_1") (pintype "passive"))
      (node (ref "U2") (pin "6") (pinfunction "A_6") (pintype "bidirectional"))
    )
    (net (code "6") (name "/485-B") (class "Default")
      (node (ref "R1") (pin "2") (pinfunction "2_2") (pintype "passive"))
      (node (ref "RS2") (pin "2") (pinfunction "2_2") (pintype "passive"))
      (node (ref "U2") (pin "7") (pinfunction "~{B}_7") (pintype "bidirectional"))
    )
    (net (code "7") (name "/AD-Vout0") (class "Default")
      (node (ref "*9") (pin "5") (pinfunction "AIN1_5") (pintype "passive"))
      (node (ref "U8") (pin "6") (pinfunction "OUT_6") (pintype "output"))
    )
    (net (code "8") (name "/CANH") (class "Default")
      (node (ref "CAN1") (pin "1") (pinfunction "1_1") (pintype "passive"))
      (node (ref "R28") (pin "1") (pinfunction "1_1") (pintype "passive"))
      (node (ref "U10") (pin "7") (pinfunction "CANH_7") (pintype "passive"))
    )
    (net (code "9") (name "/CANL") (class "Default")
      (node (ref "CAN1") (pin "2") (pinfunction "2_2") (pintype "passive"))
      (node (ref "R28") (pin "2") (pinfunction "2_2") (pintype "passive"))
      (node (ref "U10") (pin "6") (pinfunction "CANL_6") (pintype "passive"))
    )
    (net (code "10") (name "/CANRX") (class "Default")
      (node (ref "U10") (pin "4") (pinfunction "RXD_4") (pintype "passive"))
      (node (ref "U5") (pin "44") (pinfunction "PA11_44") (pintype "bidirectional"))
    )
    (net (code "11") (name "/CANTX") (class "Default")
      (node (ref "U10") (pin "1") (pinfunction "TXD_1") (pintype "passive"))
      (node (ref "U5") (pin "45") (pinfunction "PA12_45") (pintype "bidirectional"))
    )
    (net (code "12") (name "/CH340 D+") (class "Default")
      (node (ref "U9") (pin "5") (pinfunction "UD+_5") (pintype "passive"))
      (node (ref "USB_USART1") (pin "3") (pinfunction "D+_3") (pintype "passive"))
    )
    (net (code "13") (name "/CH340 D-") (class "Default")
      (node (ref "U9") (pin "6") (pinfunction "UD-_6") (pintype "passive"))
      (node (ref "USB_USART1") (pin "2") (pinfunction "D-_2") (pintype "passive"))
    )
    (net (code "14") (name "/Current0") (class "Default")
      (node (ref "*9") (pin "4") (pinfunction "AIN0_4") (pintype "passive"))
      (node (ref "U7") (pin "6") (pinfunction "OUT_6") (pintype "output"))
    )
    (net (code "15") (name "/DA0") (class "Default")
      (node (ref "*1") (pin "3") (pinfunction "VoutA_3") (pintype "passive"))
      (node (ref "*4") (pin "5") (pinfunction "+IN_5") (pintype "passive"))
    )
    (net (code "16") (name "/DA1") (class "Default")
      (node (ref "*1") (pin "23") (pinfunction "VoutB_23") (pintype "passive"))
      (node (ref "*3") (pin "5") (pinfunction "+IN_5") (pintype "passive"))
    )
    (net (code "17") (name "/DA_CLR#") (class "Default")
      (node (ref "*1") (pin "11") (pinfunction "CLR#_11") (pintype "passive"))
      (node (ref "U5") (pin "29") (pinfunction "PB10_29") (pintype "bidirectional"))
    )
    (net (code "18") (name "/DA_LDAC#") (class "Default")
      (node (ref "*1") (pin "10") (pinfunction "LDAC#_10") (pintype "passive"))
      (node (ref "U5") (pin "30") (pinfunction "PB11_30") (pintype "bidirectional"))
    )
    (net (code "19") (name "/DA_SCLK") (class "Default")
      (node (ref "*1") (pin "8") (pinfunction "SCLK_8") (pintype "passive"))
      (node (ref "R22") (pin "1") (pinfunction "1_1") (pintype "passive"))
      (node (ref "U5") (pin "34") (pinfunction "PB13_34") (pintype "bidirectional"))
    )
    (net (code "20") (name "/DA_SDIN") (class "Default")
      (node (ref "*1") (pin "9") (pinfunction "SDIN_9") (pintype "passive"))
      (node (ref "R25") (pin "1") (pinfunction "1_1") (pintype "passive"))
      (node (ref "U5") (pin "36") (pinfunction "PB15_36") (pintype "bidirectional"))
    )
    (net (code "21") (name "/DA_SDO") (class "Default")
      (node (ref "*1") (pin "16") (pinfunction "SDO_16") (pintype "passive"))
      (node (ref "R23") (pin "1") (pinfunction "1_1") (pintype "passive"))
      (node (ref "U5") (pin "35") (pinfunction "PB14_35") (pintype "bidirectional"))
    )
    (net (code "22") (name "/DA_SYNC#") (class "Default")
      (node (ref "*1") (pin "7") (pinfunction "SYNC#_7") (pintype "passive"))
      (node (ref "U5") (pin "33") (pinfunction "PB12_33") (pintype "bidirectional"))
    )
    (net (code "23") (name "/Force+") (class "Default")
      (node (ref "Force Sensor1") (pin "1") (pinfunction "1_1") (pintype "passive"))
      (node (ref "U6") (pin "3") (pinfunction "+IN_3") (pintype "input"))
    )
    (net (code "24") (name "/Force-") (class "Default")
      (node (ref "Force Sensor1") (pin "2") (pinfunction "2_2") (pintype "passive"))
      (node (ref "U6") (pin "2") (pinfunction "-IN_2") (pintype "input"))
    )
    (net (code "25") (name "/Force0") (class "Default")
      (node (ref "*9") (pin "6") (pinfunction "AIN2_6") (pintype "passive"))
      (node (ref "U6") (pin "6") (pinfunction "OUT_6") (pintype "output"))
    )
    (net (code "26") (name "/KEY1") (class "Default")
      (node (ref "C20") (pin "1") (pinfunction "1_1") (pintype "passive"))
      (node (ref "R5") (pin "2") (pinfunction "2_2") (pintype "passive"))
      (node (ref "S1") (pin "1") (pinfunction "1_1") (pintype "passive"))
      (node (ref "U5") (pin "10") (pinfunction "PC2_10") (pintype "bidirectional"))
    )
    (net (code "27") (name "/LED_G") (class "Default")
      (node (ref "D2") (pin "K") (pinfunction "K_K") (pintype "passive"))
      (node (ref "U5") (pin "9") (pinfunction "PC1_9") (pintype "bidirectional"))
    )
    (net (code "28") (name "/LED_R") (class "Default")
      (node (ref "D3") (pin "K") (pinfunction "K_K") (pintype "passive"))
      (node (ref "U5") (pin "8") (pinfunction "PC0_8") (pintype "bidirectional"))
    )
    (net (code "29") (name "/NRST") (class "Default")
      (node (ref "C39") (pin "1") (pinfunction "1_1") (pintype "passive"))
      (node (ref "R26") (pin "2") (pinfunction "2_2") (pintype "passive"))
      (node (ref "RESET1") (pin "1") (pinfunction "1_1") (pintype "passive"))
      (node (ref "U5") (pin "7") (pinfunction "NRST_7") (pintype "bidirectional"))
    )
    (net (code "30") (name "/OSC_IN") (class "Default")
      (node (ref "C47") (pin "2") (pinfunction "2_2") (pintype "passive"))
      (node (ref "U5") (pin "5") (pinfunction "PH0-OSC_IN(PH0)_5") (pintype "bidirectional"))
      (node (ref "Y2") (pin "3") (pinfunction "OSC2_3") (pintype "passive"))
    )
    (net (code "31") (name "/OSC_OUT") (class "Default")
      (node (ref "C48") (pin "2") (pinfunction "2_2") (pintype "passive"))
      (node (ref "U5") (pin "6") (pinfunction "PH1-OSC_OUT(PH1)_6") (pintype "bidirectional"))
      (node (ref "Y2") (pin "1") (pinfunction "OSC1_1") (pintype "passive"))
    )
    (net (code "32") (name "/PD2") (class "Default")
      (node (ref "U2") (pin "2") (pinfunction "~{RE}_2") (pintype "input"))
      (node (ref "U2") (pin "3") (pinfunction "DE_3") (pintype "input"))
      (node (ref "U5") (pin "54") (pinfunction "PD2_54") (pintype "bidirectional"))
    )
    (net (code "33") (name "/RDY0") (class "Default")
      (node (ref "*9") (pin "2") (pinfunction "RDY_2") (pintype "passive"))
      (node (ref "R16") (pin "1") (pinfunction "1_1") (pintype "passive"))
      (node (ref "U5") (pin "57") (pinfunction "PB5_57") (pintype "bidirectional"))
    )
    (net (code "34") (name "/RXD") (class "Default")
      (node (ref "U5") (pin "43") (pinfunction "PA10_43") (pintype "bidirectional"))
      (node (ref "U9") (pin "2") (pinfunction "TXD_2") (pintype "passive"))
    )
    (net (code "35") (name "/RXD2") (class "Default")
      (node (ref "U1") (pin "12") (pinfunction "R1OUT_12") (pintype "output"))
      (node (ref "U5") (pin "17") (pinfunction "PA3_17") (pintype "bidirectional"))
    )
    (net (code "36") (name "/RXD2_In") (class "Default")
      (node (ref "RS1") (pin "5") (pinfunction "5_5") (pintype "passive"))
      (node (ref "U1") (pin "13") (pinfunction "R1IN_13") (pintype "input"))
    )
    (net (code "37") (name "/RXD3") (class "Default")
      (node (ref "U2") (pin "1") (pinfunction "RO_1") (pintype "output"))
      (node (ref "U5") (pin "52") (pinfunction "PC11_52") (pintype "bidirectional"))
    )
    (net (code "38") (name "/SCL") (class "Default")
      (node (ref "*10") (pin "6") (pinfunction "SCL_6") (pintype "passive"))
      (node (ref "*9") (pin "10") (pinfunction "SCL_10") (pintype "passive"))
      (node (ref "R17") (pin "1") (pinfunction "1_1") (pintype "passive"))
      (node (ref "U5") (pin "58") (pinfunction "PB6_58") (pintype "bidirectional"))
    )
    (net (code "39") (name "/SDA") (class "Default")
      (node (ref "*10") (pin "1") (pinfunction "SDA_1") (pintype "passive"))
      (node (ref "*9") (pin "9") (pinfunction "SDA_9") (pintype "passive"))
      (node (ref "R21") (pin "1") (pinfunction "1_1") (pintype "passive"))
      (node (ref "U5") (pin "59") (pinfunction "PB7_59") (pintype "bidirectional"))
    )
    (net (code "40") (name "/SWCLK") (class "Default")
      (node (ref "SWD1") (pin "4") (pinfunction "4_4") (pintype "passive"))
      (node (ref "U5") (pin "49") (pinfunction "PA14(JTCK-SWCLK)_49") (pintype "bidirectional"))
    )
    (net (code "41") (name "/SWDIO") (class "Default")
      (node (ref "SWD1") (pin "2") (pinfunction "2_2") (pintype "passive"))
      (node (ref "U5") (pin "46") (pinfunction "PA13(JTMS-SWDIO)_46") (pintype "bidirectional"))
    )
    (net (code "42") (name "/TXD") (class "Default")
      (node (ref "U5") (pin "42") (pinfunction "PA9_42") (pintype "bidirectional"))
      (node (ref "U9") (pin "3") (pinfunction "RXD_3") (pintype "passive"))
    )
    (net (code "43") (name "/TXD2") (class "Default")
      (node (ref "U1") (pin "11") (pinfunction "T1IN_11") (pintype "input"))
      (node (ref "U5") (pin "16") (pinfunction "PA2_16") (pintype "bidirectional"))
    )
    (net (code "44") (name "/TXD2_Out") (class "Default")
      (node (ref "RS1") (pin "3") (pinfunction "3_3") (pintype "passive"))
      (node (ref "U1") (pin "14") (pinfunction "T1OUT_14") (pintype "output"))
    )
    (net (code "45") (name "/TXD3") (class "Default")
      (node (ref "U2") (pin "4") (pinfunction "DI_4") (pintype "input"))
      (node (ref "U5") (pin "51") (pinfunction "PC10_51") (pintype "bidirectional"))
    )
    (net (code "46") (name "/Vout0") (class "Default")
      (node (ref "DA1") (pin "1") (pinfunction "1_1") (pintype "passive"))
      (node (ref "R7") (pin "2") (pinfunction "2_2") (pintype "passive"))
      (node (ref "R9") (pin "1") (pinfunction "1_1") (pintype "passive"))
      (node (ref "U7") (pin "2") (pinfunction "-IN_2") (pintype "input"))
    )
    (net (code "47") (name "/Vout1") (class "Default")
      (node (ref "*3") (pin "15") (pinfunction "Vout_15") (pintype "passive"))
      (node (ref "*3") (pin "16") (pinfunction "Vout_16") (pintype "passive"))
      (node (ref "*3") (pin "6") (pinfunction "-IN_6") (pintype "passive"))
      (node (ref "DA2") (pin "1") (pinfunction "1_1") (pintype "passive"))
    )
    (net (code "48") (name "2.5V") (class "Default")
      (node (ref "*1") (pin "17") (pinfunction "REFIN_17") (pintype "passive"))
      (node (ref "*2") (pin "2") (pinfunction "V+_2") (pintype "passive"))
      (node (ref "C6") (pin "2") (pinfunction "2_2") (pintype "passive"))
      (node (ref "R2") (pin "1") (pinfunction "1_1") (pintype "passive"))
    )
    (net (code "49") (name "3.3V") (class "Default")
      (node (ref "*10") (pin "5") (pinfunction "VDD_5") (pintype "passive"))
      (node (ref "C28") (pin "2") (pinfunction "2_2") (pintype "passive"))
      (node (ref "C29") (pin "2") (pinfunction "2_2") (pintype "passive"))
      (node (ref "C50") (pin "1") (pinfunction "1_1") (pintype "passive"))
      (node (ref "C51") (pin "1") (pinfunction "1_1") (pintype "passive"))
      (node (ref "C53") (pin "1") (pinfunction "1_1") (pintype "passive"))
      (node (ref "C54") (pin "1") (pinfunction "1_1") (pintype "passive"))
      (node (ref "L4") (pin "2") (pinfunction "2_2") (pintype "passive"))
      (node (ref "R16") (pin "2") (pinfunction "2_2") (pintype "passive"))
      (node (ref "R17") (pin "2") (pinfunction "2_2") (pintype "passive"))
      (node (ref "R21") (pin "2") (pinfunction "2_2") (pintype "passive"))
      (node (ref "R22") (pin "2") (pinfunction "2_2") (pintype "passive"))
      (node (ref "R23") (pin "2") (pinfunction "2_2") (pintype "passive"))
      (node (ref "R25") (pin "2") (pinfunction "2_2") (pintype "passive"))
      (node (ref "R26") (pin "1") (pinfunction "1_1") (pintype "passive"))
      (node (ref "R3") (pin "1") (pinfunction "1_1") (pintype "passive"))
      (node (ref "R4") (pin "1") (pinfunction "1_1") (pintype "passive"))
      (node (ref "R5") (pin "1") (pinfunction "1_1") (pintype "passive"))
      (node (ref "U5") (pin "1") (pinfunction "VBAT_1") (pintype "power_in"))
      (node (ref "U5") (pin "19") (pinfunction "VDD_19") (pintype "power_in"))
      (node (ref "U5") (pin "32") (pinfunction "VDD_32") (pintype "power_in"))
      (node (ref "U5") (pin "48") (pinfunction "VDD_48") (pintype "power_in"))
      (node (ref "U5") (pin "64") (pinfunction "VDD_64") (pintype "power_in"))
      (node (ref "VR1") (pin "2") (pinfunction "Vout_2") (pintype "passive"))
    )
    (net (code "50") (name "GND") (class "Default")
      (node (ref "*1") (pin "15") (pinfunction "GND_15") (pintype "passive"))
      (node (ref "*10") (pin "2") (pinfunction "VSS_2") (pintype "passive"))
      (node (ref "*5") (pin "2") (pinfunction "2_2") (pintype "passive"))
      (node (ref "C1") (pin "1") (pinfunction "1_1") (pintype "passive"))
      (node (ref "C18") (pin "2") (pinfunction "2_2") (pintype "passive"))
      (node (ref "C19") (pin "1") (pinfunction "1_1") (pintype "passive"))
      (node (ref "C20") (pin "2") (pinfunction "2_2") (pintype "passive"))
      (node (ref "C22") (pin "1") (pinfunction "1_1") (pintype "passive"))
      (node (ref "C23") (pin "2") (pinfunction "2_2") (pintype "passive"))
      (node (ref "C26") (pin "1") (pinfunction "1_1") (pintype "passive"))
      (node (ref "C27") (pin "1") (pinfunction "1_1") (pintype "passive"))
      (node (ref "C28") (pin "1") (pinfunction "1_1") (pintype "passive"))
      (node (ref "C29") (pin "1") (pinfunction "1_1") (pintype "passive"))
      (node (ref "C3") (pin "2") (pinfunction "2_2") (pintype "passive"))
      (node (ref "C39") (pin "2") (pinfunction "2_2") (pintype "passive"))
      (node (ref "C40") (pin "2") (pinfunction "2_2") (pintype "passive"))
      (node (ref "C41") (pin "2") (pinfunction "2_2") (pintype "passive"))
      (node (ref "C42") (pin "1") (pinfunction "1_1") (pintype "passive"))
      (node (ref "C43") (pin "2") (pinfunction "2_2") (pintype "passive"))
      (node (ref "C45") (pin "1") (pinfunction "1_1") (pintype "passive"))
      (node (ref "C46") (pin "1") (pinfunction "1_1") (pintype "passive"))
      (node (ref "C47") (pin "1") (pinfunction "1_1") (pintype "passive"))
      (node (ref "C48") (pin "1") (pinfunction "1_1") (pintype "passive"))
      (node (ref "C49") (pin "1") (pinfunction "1_1") (pintype "passive"))
      (node (ref "C5") (pin "2") (pinfunction "2_2") (pintype "passive"))
      (node (ref "C50") (pin "2") (pinfunction "2_2") (pintype "passive"))
      (node (ref "C51") (pin "2") (pinfunction "2_2") (pintype "passive"))
      (node (ref "C52") (pin "2") (pinfunction "2_2") (pintype "passive"))
      (node (ref "C53") (pin "2") (pinfunction "2_2") (pintype "passive"))
      (node (ref "C54") (pin "2") (pinfunction "2_2") (pintype "passive"))
      (node (ref "C7") (pin "1") (pinfunction "1_1") (pintype "passive"))
      (node (ref "C8") (pin "2") (pinfunction "2_2") (pintype "passive"))
      (node (ref "C9") (pin "2") (pinfunction "2_2") (pintype "passive"))
      (node (ref "D1") (pin "1") (pinfunction "A_1") (pintype "passive"))
      (node (ref "D7") (pin "1") (pinfunction "A_1") (pintype "passive"))
      (node (ref "D8") (pin "2") (pinfunction "K_2") (pintype "passive"))
      (node (ref "D9") (pin "K") (pinfunction "K_K") (pintype "passive"))
      (node (ref "L2") (pin "2") (pinfunction "2_2") (pintype "passive"))
      (node (ref "L3") (pin "1") (pinfunction "1_1") (pintype "passive"))
      (node (ref "R27") (pin "1") (pinfunction "1_1") (pintype "passive"))
      (node (ref "RESET1") (pin "2") (pinfunction "2_2") (pintype "passive"))
      (node (ref "RS1") (pin "4") (pinfunction "4_4") (pintype "passive"))
      (node (ref "RS2") (pin "3") (pinfunction "3_3") (pintype "passive"))
      (node (ref "S1") (pin "2") (pinfunction "2_2") (pintype "passive"))
      (node (ref "SWD1") (pin "3") (pinfunction "3_3") (pintype "passive"))
      (node (ref "U1") (pin "15") (pinfunction "GND_15") (pintype "power_in"))
      (node (ref "U10") (pin "2") (pinfunction "GND_2") (pintype "passive"))
      (node (ref "U10") (pin "8") (pinfunction "S_8") (pintype "passive"))
      (node (ref "U2") (pin "5") (pinfunction "GND_5") (pintype "power_in"))
      (node (ref "U3") (pin "3") (pinfunction "GND_3") (pintype "power_in"))
      (node (ref "U3") (pin "5") (pinfunction "~{ON}/OFF_5") (pintype "input"))
      (node (ref "U3") (pin "6") (pinfunction "6_6") (pintype "power_in"))
      (node (ref "U4") (pin "4") (pinfunction "FB_4") (pintype "input"))
      (node (ref "U5") (pin "12") (pinfunction "VSSA_12") (pintype "power_in"))
      (node (ref "U5") (pin "18") (pinfunction "VSS_18") (pintype "power_in"))
      (node (ref "U5") (pin "63") (pinfunction "VSS_63") (pintype "power_in"))
      (node (ref "U9") (pin "1") (pinfunction "GND_1") (pintype "passive"))
      (node (ref "USB_USART1") (pin "5") (pinfunction "VSS_5") (pintype "passive"))
      (node (ref "VR1") (pin "1") (pinfunction "GND_1") (pintype "passive"))
    )
    (net (code "51") (name "Net-(*3-E{slash}S#)") (class "Default")
      (node (ref "*3") (pin "4") (pinfunction "E/S#_4") (pintype "passive"))
      (node (ref "*3") (pin "7") (pinfunction "Vdig_7") (pintype "passive"))
      (node (ref "D5") (pin "2") (pinfunction "K_2") (pintype "passive"))
      (node (ref "R6") (pin "1") (pinfunction "1_1") (pintype "passive"))
    )
    (net (code "52") (name "Net-(*3-Iset)") (class "Default")
      (node (ref "*3") (pin "9") (pinfunction "Iset_9") (pintype "passive"))
      (node (ref "C24") (pin "2") (pinfunction "2_2") (pintype "passive"))
      (node (ref "R10") (pin "2") (pinfunction "2_2") (pintype "passive"))
    )
    (net (code "53") (name "Net-(*4--IN)") (class "Default")
      (node (ref "*4") (pin "15") (pinfunction "Vout_15") (pintype "passive"))
      (node (ref "*4") (pin "16") (pinfunction "Vout_16") (pintype "passive"))
      (node (ref "*4") (pin "6") (pinfunction "-IN_6") (pintype "passive"))
      (node (ref "R7") (pin "1") (pinfunction "1_1") (pintype "passive"))
      (node (ref "U7") (pin "3") (pinfunction "+IN_3") (pintype "input"))
    )
    (net (code "54") (name "Net-(*4-E{slash}S#)") (class "Default")
      (node (ref "*4") (pin "4") (pinfunction "E/S#_4") (pintype "passive"))
      (node (ref "*4") (pin "7") (pinfunction "Vdig_7") (pintype "passive"))
      (node (ref "D6") (pin "2") (pinfunction "K_2") (pintype "passive"))
      (node (ref "R8") (pin "1") (pinfunction "1_1") (pintype "passive"))
    )
    (net (code "55") (name "Net-(*4-Iset)") (class "Default")
      (node (ref "*4") (pin "9") (pinfunction "Iset_9") (pintype "passive"))
      (node (ref "C25") (pin "2") (pinfunction "2_2") (pintype "passive"))
      (node (ref "R11") (pin "2") (pinfunction "2_2") (pintype "passive"))
    )
    (net (code "56") (name "Net-(*6-V+)") (class "Default")
      (node (ref "*6") (pin "2") (pinfunction "V+_2") (pintype "passive"))
      (node (ref "C30") (pin "2") (pinfunction "2_2") (pintype "passive"))
      (node (ref "R18") (pin "1") (pinfunction "1_1") (pintype "passive"))
      (node (ref "U7") (pin "5") (pinfunction "REF_5") (pintype "input"))
    )
    (net (code "57") (name "Net-(*7-V+)") (class "Default")
      (node (ref "*7") (pin "2") (pinfunction "V+_2") (pintype "passive"))
      (node (ref "C31") (pin "2") (pinfunction "2_2") (pintype "passive"))
      (node (ref "R19") (pin "1") (pinfunction "1_1") (pintype "passive"))
      (node (ref "U8") (pin "5") (pinfunction "REF_5") (pintype "input"))
    )
    (net (code "58") (name "Net-(*8-V+)") (class "Default")
      (node (ref "*8") (pin "2") (pinfunction "V+_2") (pintype "passive"))
      (node (ref "C32") (pin "2") (pinfunction "2_2") (pintype "passive"))
      (node (ref "R20") (pin "1") (pinfunction "1_1") (pintype "passive"))
      (node (ref "U6") (pin "5") (pinfunction "REF_5") (pintype "input"))
    )
    (net (code "59") (name "Net-(D1-K)") (class "Default")
      (node (ref "D1") (pin "2") (pinfunction "K_2") (pintype "passive"))
      (node (ref "L1") (pin "1") (pinfunction "1_1") (pintype "passive"))
      (node (ref "U3") (pin "2") (pinfunction "OUT_2") (pintype "power_in"))
    )
    (net (code "60") (name "Net-(D2-PadA)") (class "Default")
      (node (ref "D2") (pin "A") (pinfunction "A_A") (pintype "passive"))
      (node (ref "R3") (pin "2") (pinfunction "2_2") (pintype "passive"))
    )
    (net (code "61") (name "Net-(D3-PadA)") (class "Default")
      (node (ref "D3") (pin "A") (pinfunction "A_A") (pintype "passive"))
      (node (ref "R4") (pin "2") (pinfunction "2_2") (pintype "passive"))
    )
    (net (code "62") (name "Net-(D4-K)") (class "Default")
      (node (ref "D4") (pin "2") (pinfunction "K_2") (pintype "passive"))
      (node (ref "L2") (pin "1") (pinfunction "1_1") (pintype "passive"))
      (node (ref "U4") (pin "2") (pinfunction "OUT_2") (pintype "power_in"))
    )
    (net (code "63") (name "Net-(D9-PadA)") (class "Default")
      (node (ref "D9") (pin "A") (pinfunction "A_A") (pintype "passive"))
      (node (ref "R24") (pin "2") (pinfunction "2_2") (pintype "passive"))
    )
    (net (code "64") (name "Net-(R13-Pad1)") (class "Default")
      (node (ref "R13") (pin "1") (pinfunction "1_1") (pintype "passive"))
      (node (ref "U8") (pin "1") (pinfunction "RG_1") (pintype "passive"))
    )
    (net (code "65") (name "Net-(R13-Pad2)") (class "Default")
      (node (ref "R13") (pin "2") (pinfunction "2_2") (pintype "passive"))
      (node (ref "U8") (pin "8") (pinfunction "RG_8") (pintype "passive"))
    )
    (net (code "66") (name "Net-(R14-Pad1)") (class "Default")
      (node (ref "R14") (pin "1") (pinfunction "1_1") (pintype "passive"))
      (node (ref "U7") (pin "1") (pinfunction "RG_1") (pintype "passive"))
    )
    (net (code "67") (name "Net-(R14-Pad2)") (class "Default")
      (node (ref "R14") (pin "2") (pinfunction "2_2") (pintype "passive"))
      (node (ref "U7") (pin "8") (pinfunction "RG_8") (pintype "passive"))
    )
    (net (code "68") (name "Net-(R15-Pad1)") (class "Default")
      (node (ref "R15") (pin "1") (pinfunction "1_1") (pintype "passive"))
      (node (ref "U6") (pin "1") (pinfunction "RG_1") (pintype "passive"))
    )
    (net (code "69") (name "Net-(R15-Pad2)") (class "Default")
      (node (ref "R15") (pin "2") (pinfunction "2_2") (pintype "passive"))
      (node (ref "U6") (pin "8") (pinfunction "RG_8") (pintype "passive"))
    )
    (net (code "70") (name "Net-(U1-C1+)") (class "Default")
      (node (ref "C2") (pin "2") (pinfunction "2_2") (pintype "passive"))
      (node (ref "U1") (pin "1") (pinfunction "C1+_1") (pintype "passive"))
    )
    (net (code "71") (name "Net-(U1-C1-)") (class "Default")
      (node (ref "C2") (pin "1") (pinfunction "1_1") (pintype "passive"))
      (node (ref "U1") (pin "3") (pinfunction "C1-_3") (pintype "passive"))
    )
    (net (code "72") (name "Net-(U1-C2+)") (class "Default")
      (node (ref "C4") (pin "1") (pinfunction "1_1") (pintype "passive"))
      (node (ref "U1") (pin "4") (pinfunction "C2+_4") (pintype "passive"))
    )
    (net (code "73") (name "Net-(U1-C2-)") (class "Default")
      (node (ref "C4") (pin "2") (pinfunction "2_2") (pintype "passive"))
      (node (ref "U1") (pin "5") (pinfunction "C2-_5") (pintype "passive"))
    )
    (net (code "74") (name "Net-(U1-V+)") (class "Default")
      (node (ref "C5") (pin "1") (pinfunction "1_1") (pintype "passive"))
      (node (ref "U1") (pin "2") (pinfunction "V+_2") (pintype "power_in"))
    )
    (net (code "75") (name "Net-(U1-V-)") (class "Default")
      (node (ref "C8") (pin "1") (pinfunction "1_1") (pintype "passive"))
      (node (ref "U1") (pin "6") (pinfunction "V-_6") (pintype "power_in"))
    )
    (net (code "76") (name "Net-(U5A-BOOT0)") (class "Default")
      (node (ref "R27") (pin "2") (pinfunction "2_2") (pintype "passive"))
      (node (ref "U5") (pin "60") (pinfunction "BOOT0_60") (pintype "input"))
    )
    (net (code "77") (name "Net-(U5A-VCAP_1)") (class "Default")
      (node (ref "C40") (pin "1") (pinfunction "1_1") (pintype "passive"))
      (node (ref "U5") (pin "31") (pinfunction "VCAP_1_31") (pintype "power_in"))
    )
    (net (code "78") (name "Net-(U5A-VCAP_2)") (class "Default")
      (node (ref "C41") (pin "1") (pinfunction "1_1") (pintype "passive"))
      (node (ref "U5") (pin "47") (pinfunction "VCAP_2_47") (pintype "power_in"))
    )
    (net (code "79") (name "Net-(U5B-VDDA)") (class "Default")
      (node (ref "C52") (pin "1") (pinfunction "1_1") (pintype "passive"))
      (node (ref "L4") (pin "1") (pinfunction "1_1") (pintype "passive"))
      (node (ref "U5") (pin "13") (pinfunction "VDDA_13") (pintype "power_in"))
    )
    (net (code "80") (name "Net-(U8-+IN)") (class "Default")
      (node (ref "R12") (pin "1") (pinfunction "1_1") (pintype "passive"))
      (node (ref "R9") (pin "2") (pinfunction "2_2") (pintype "passive"))
      (node (ref "U8") (pin "3") (pinfunction "+IN_3") (pintype "input"))
    )
    (net (code "81") (name "Net-(U9-V3.3)") (class "Default")
      (node (ref "C43") (pin "1") (pinfunction "1_1") (pintype "passive"))
      (node (ref "U9") (pin "4") (pinfunction "V3.3_4") (pintype "passive"))
    )
    (net (code "82") (name "Net-(U9-XI)") (class "Default")
      (node (ref "C45") (pin "2") (pinfunction "2_2") (pintype "passive"))
      (node (ref "U9") (pin "7") (pinfunction "XI_7") (pintype "passive"))
      (node (ref "Y1") (pin "1") (pinfunction "OSC1_1") (pintype "passive"))
    )
    (net (code "83") (name "Net-(U9-XO)") (class "Default")
      (node (ref "C46") (pin "2") (pinfunction "2_2") (pintype "passive"))
      (node (ref "U9") (pin "8") (pinfunction "XO_8") (pintype "passive"))
      (node (ref "Y1") (pin "3") (pinfunction "OSC2_3") (pintype "passive"))
    )
    (net (code "84") (name "SGND") (class "Default")
      (node (ref "*1") (pin "18") (pinfunction "DAC_GND_18") (pintype "passive"))
      (node (ref "*1") (pin "19") (pinfunction "DAC_GND_19") (pintype "passive"))
      (node (ref "*1") (pin "20") (pinfunction "SIG_GND_20") (pintype "passive"))
      (node (ref "*1") (pin "21") (pinfunction "SIG_GND_21") (pintype "passive"))
      (node (ref "*2") (pin "1") (pinfunction "V-_1") (pintype "passive"))
      (node (ref "*6") (pin "1") (pinfunction "V-_1") (pintype "passive"))
      (node (ref "*7") (pin "1") (pinfunction "V-_1") (pintype "passive"))
      (node (ref "*8") (pin "1") (pinfunction "V-_1") (pintype "passive"))
      (node (ref "*9") (pin "1") (pinfunction "ADDR_1") (pintype "passive"))
      (node (ref "*9") (pin "3") (pinfunction "GND_3") (pintype "passive"))
      (node (ref "*9") (pin "7") (pinfunction "AIN3_7") (pintype "passive"))
      (node (ref "C10") (pin "2") (pinfunction "2_2") (pintype "passive"))
      (node (ref "C11") (pin "1") (pinfunction "1_1") (pintype "passive"))
      (node (ref "C12") (pin "1") (pinfunction "1_1") (pintype "passive"))
      (node (ref "C13") (pin "1") (pinfunction "1_1") (pintype "passive"))
      (node (ref "C14") (pin "2") (pinfunction "2_2") (pintype "passive"))
      (node (ref "C15") (pin "1") (pinfunction "1_1") (pintype "passive"))
      (node (ref "C16") (pin "1") (pinfunction "1_1") (pintype "passive"))
      (node (ref "C17") (pin "1") (pinfunction "1_1") (pintype "passive"))
      (node (ref "C30") (pin "1") (pinfunction "1_1") (pintype "passive"))
      (node (ref "C31") (pin "1") (pinfunction "1_1") (pintype "passive"))
      (node (ref "C32") (pin "1") (pinfunction "1_1") (pintype "passive"))
      (node (ref "C33") (pin "1") (pinfunction "1_1") (pintype "passive"))
      (node (ref "C34") (pin "1") (pinfunction "1_1") (pintype "passive"))
      (node (ref "C35") (pin "1") (pinfunction "1_1") (pintype "passive"))
      (node (ref "C36") (pin "1") (pinfunction "1_1") (pintype "passive"))
      (node (ref "C37") (pin "1") (pinfunction "1_1") (pintype "passive"))
      (node (ref "C38") (pin "1") (pinfunction "1_1") (pintype "passive"))
      (node (ref "C44") (pin "2") (pinfunction "2_2") (pintype "passive"))
      (node (ref "C6") (pin "1") (pinfunction "1_1") (pintype "passive"))
      (node (ref "DA1") (pin "2") (pinfunction "2_2") (pintype "passive"))
      (node (ref "DA2") (pin "2") (pinfunction "2_2") (pintype "passive"))
      (node (ref "Force Sensor1") (pin "4") (pinfunction "4_4") (pintype "passive"))
      (node (ref "L3") (pin "2") (pinfunction "2_2") (pintype "passive"))
      (node (ref "R12") (pin "2") (pinfunction "2_2") (pintype "passive"))
      (node (ref "U8") (pin "2") (pinfunction "-IN_2") (pintype "input"))
    )
    (net (code "85") (name "unconnected-(*1-NC-Pad2)") (class "Default")
      (node (ref "*1") (pin "2") (pinfunction "NC_2") (pintype "passive"))
    )
    (net (code "86") (name "unconnected-(*1-NC-Pad4)") (class "Default")
      (node (ref "*1") (pin "4") (pinfunction "NC_4") (pintype "passive"))
    )
    (net (code "87") (name "unconnected-(*1-NC-Pad6)") (class "Default")
      (node (ref "*1") (pin "6") (pinfunction "NC_6") (pintype "passive"))
    )
    (net (code "88") (name "unconnected-(*1-NC-Pad12)") (class "Default")
      (node (ref "*1") (pin "12") (pinfunction "NC_12") (pintype "passive"))
    )
    (net (code "89") (name "unconnected-(*1-NC-Pad13)") (class "Default")
      (node (ref "*1") (pin "13") (pinfunction "NC_13") (pintype "passive"))
    )
    (net (code "90") (name "unconnected-(*1-NC-Pad22)") (class "Default")
      (node (ref "*1") (pin "22") (pinfunction "NC_22") (pintype "passive"))
    )
    (net (code "91") (name "unconnected-(*2-ADJ-Pad3)") (class "Default")
      (node (ref "*2") (pin "3") (pinfunction "ADJ_3") (pintype "passive"))
    )
    (net (code "92") (name "unconnected-(*3-Iflag-Pad8)") (class "Default")
      (node (ref "*3") (pin "8") (pinfunction "Iflag_8") (pintype "passive"))
    )
    (net (code "93") (name "unconnected-(*3-Tflag-Pad3)") (class "Default")
      (node (ref "*3") (pin "3") (pinfunction "Tflag_3") (pintype "passive"))
    )
    (net (code "94") (name "unconnected-(*3-Tsense-Pad12)") (class "Default")
      (node (ref "*3") (pin "12") (pinfunction "Tsense_12") (pintype "passive"))
    )
    (net (code "95") (name "unconnected-(*4-Iflag-Pad8)") (class "Default")
      (node (ref "*4") (pin "8") (pinfunction "Iflag_8") (pintype "passive"))
    )
    (net (code "96") (name "unconnected-(*4-Tflag-Pad3)") (class "Default")
      (node (ref "*4") (pin "3") (pinfunction "Tflag_3") (pintype "passive"))
    )
    (net (code "97") (name "unconnected-(*4-Tsense-Pad12)") (class "Default")
      (node (ref "*4") (pin "12") (pinfunction "Tsense_12") (pintype "passive"))
    )
    (net (code "98") (name "unconnected-(*6-ADJ-Pad3)") (class "Default")
      (node (ref "*6") (pin "3") (pinfunction "ADJ_3") (pintype "passive"))
    )
    (net (code "99") (name "unconnected-(*7-ADJ-Pad3)") (class "Default")
      (node (ref "*7") (pin "3") (pinfunction "ADJ_3") (pintype "passive"))
    )
    (net (code "100") (name "unconnected-(*8-ADJ-Pad3)") (class "Default")
      (node (ref "*8") (pin "3") (pinfunction "ADJ_3") (pintype "passive"))
    )
    (net (code "101") (name "unconnected-(*10-NC-Pad3)") (class "Default")
      (node (ref "*10") (pin "3") (pinfunction "NC_3") (pintype "passive"))
    )
    (net (code "102") (name "unconnected-(*10-NC-Pad4)") (class "Default")
      (node (ref "*10") (pin "4") (pinfunction "NC_4") (pintype "passive"))
    )
    (net (code "103") (name "unconnected-(RS1-Pad1)") (class "Default")
      (node (ref "RS1") (pin "1") (pinfunction "1_1") (pintype "passive"))
    )
    (net (code "104") (name "unconnected-(RS1-Pad2)") (class "Default")
      (node (ref "RS1") (pin "2") (pinfunction "2_2") (pintype "passive"))
    )
    (net (code "105") (name "unconnected-(RS1-Pad6)") (class "Default")
      (node (ref "RS1") (pin "6") (pinfunction "6_6") (pintype "passive"))
    )
    (net (code "106") (name "unconnected-(T1-Pad1)") (class "Default")
      (node (ref "T1") (pin "1") (pinfunction "1_1") (pintype "passive"))
    )
    (net (code "107") (name "unconnected-(T2-Pad1)") (class "Default")
      (node (ref "T2") (pin "1") (pinfunction "1_1") (pintype "passive"))
    )
    (net (code "108") (name "unconnected-(T3-Pad1)") (class "Default")
      (node (ref "T3") (pin "1") (pinfunction "1_1") (pintype "passive"))
    )
    (net (code "109") (name "unconnected-(T4-Pad1)") (class "Default")
      (node (ref "T4") (pin "1") (pinfunction "1_1") (pintype "passive"))
    )
    (net (code "110") (name "unconnected-(U1-R2IN-Pad8)") (class "Default")
      (node (ref "U1") (pin "8") (pinfunction "R2IN_8") (pintype "input+no_connect"))
    )
    (net (code "111") (name "unconnected-(U1-R2OUT-Pad9)") (class "Default")
      (node (ref "U1") (pin "9") (pinfunction "R2OUT_9") (pintype "output"))
    )
    (net (code "112") (name "unconnected-(U1-T2IN-Pad10)") (class "Default")
      (node (ref "U1") (pin "10") (pinfunction "T2IN_10") (pintype "input+no_connect"))
    )
    (net (code "113") (name "unconnected-(U1-T2OUT-Pad7)") (class "Default")
      (node (ref "U1") (pin "7") (pinfunction "T2OUT_7") (pintype "output"))
    )
    (net (code "114") (name "unconnected-(U5A-PA0-WKUP(PA0)-Pad14)") (class "Default")
      (node (ref "U5") (pin "14") (pinfunction "PA0-WKUP(PA0)_14") (pintype "bidirectional"))
    )
    (net (code "115") (name "unconnected-(U5A-PA1-Pad15)") (class "Default")
      (node (ref "U5") (pin "15") (pinfunction "PA1_15") (pintype "bidirectional"))
    )
    (net (code "116") (name "unconnected-(U5A-PA4-Pad20)") (class "Default")
      (node (ref "U5") (pin "20") (pinfunction "PA4_20") (pintype "bidirectional"))
    )
    (net (code "117") (name "unconnected-(U5A-PA5-Pad21)") (class "Default")
      (node (ref "U5") (pin "21") (pinfunction "PA5_21") (pintype "bidirectional"))
    )
    (net (code "118") (name "unconnected-(U5A-PA6-Pad22)") (class "Default")
      (node (ref "U5") (pin "22") (pinfunction "PA6_22") (pintype "bidirectional"))
    )
    (net (code "119") (name "unconnected-(U5A-PA7-Pad23)") (class "Default")
      (node (ref "U5") (pin "23") (pinfunction "PA7_23") (pintype "bidirectional"))
    )
    (net (code "120") (name "unconnected-(U5A-PA8-Pad41)") (class "Default")
      (node (ref "U5") (pin "41") (pinfunction "PA8_41") (pintype "bidirectional"))
    )
    (net (code "121") (name "unconnected-(U5A-PA15(JTDI)-Pad50)") (class "Default")
      (node (ref "U5") (pin "50") (pinfunction "PA15(JTDI)_50") (pintype "bidirectional"))
    )
    (net (code "122") (name "unconnected-(U5A-PB0-Pad26)") (class "Default")
      (node (ref "U5") (pin "26") (pinfunction "PB0_26") (pintype "bidirectional"))
    )
    (net (code "123") (name "unconnected-(U5A-PB1-Pad27)") (class "Default")
      (node (ref "U5") (pin "27") (pinfunction "PB1_27") (pintype "bidirectional"))
    )
    (net (code "124") (name "unconnected-(U5A-PB2-BOOT1(PB2)-Pad28)") (class "Default")
      (node (ref "U5") (pin "28") (pinfunction "PB2-BOOT1(PB2)_28") (pintype "bidirectional"))
    )
    (net (code "125") (name "unconnected-(U5A-PB3(JTDO{slash}TRACESWO)-Pad55)") (class "Default")
      (node (ref "U5") (pin "55") (pinfunction "PB3(JTDO/TRACESWO)_55") (pintype "bidirectional"))
    )
    (net (code "126") (name "unconnected-(U5A-PB4(NJTRST)-Pad56)") (class "Default")
      (node (ref "U5") (pin "56") (pinfunction "PB4(NJTRST)_56") (pintype "bidirectional"))
    )
    (net (code "127") (name "unconnected-(U5A-PB8-Pad61)") (class "Default")
      (node (ref "U5") (pin "61") (pinfunction "PB8_61") (pintype "bidirectional"))
    )
    (net (code "128") (name "unconnected-(U5A-PB9-Pad62)") (class "Default")
      (node (ref "U5") (pin "62") (pinfunction "PB9_62") (pintype "bidirectional"))
    )
    (net (code "129") (name "unconnected-(U5A-PC3-Pad11)") (class "Default")
      (node (ref "U5") (pin "11") (pinfunction "PC3_11") (pintype "bidirectional"))
    )
    (net (code "130") (name "unconnected-(U5A-PC4-Pad24)") (class "Default")
      (node (ref "U5") (pin "24") (pinfunction "PC4_24") (pintype "bidirectional"))
    )
    (net (code "131") (name "unconnected-(U5A-PC5-Pad25)") (class "Default")
      (node (ref "U5") (pin "25") (pinfunction "PC5_25") (pintype "bidirectional"))
    )
    (net (code "132") (name "unconnected-(U5A-PC6-Pad37)") (class "Default")
      (node (ref "U5") (pin "37") (pinfunction "PC6_37") (pintype "bidirectional"))
    )
    (net (code "133") (name "unconnected-(U5A-PC7-Pad38)") (class "Default")
      (node (ref "U5") (pin "38") (pinfunction "PC7_38") (pintype "bidirectional"))
    )
    (net (code "134") (name "unconnected-(U5A-PC8-Pad39)") (class "Default")
      (node (ref "U5") (pin "39") (pinfunction "PC8_39") (pintype "bidirectional"))
    )
    (net (code "135") (name "unconnected-(U5A-PC9-Pad40)") (class "Default")
      (node (ref "U5") (pin "40") (pinfunction "PC9_40") (pintype "bidirectional"))
    )
    (net (code "136") (name "unconnected-(U5A-PC12-Pad53)") (class "Default")
      (node (ref "U5") (pin "53") (pinfunction "PC12_53") (pintype "bidirectional"))
    )
    (net (code "137") (name "unconnected-(U5A-PC13-Pad2)") (class "Default")
      (node (ref "U5") (pin "2") (pinfunction "PC13_2") (pintype "bidirectional"))
    )
    (net (code "138") (name "unconnected-(U5A-PC14-OSC32_IN(PC14)-Pad3)") (class "Default")
      (node (ref "U5") (pin "3") (pinfunction "PC14-OSC32_IN(PC14)_3") (pintype "bidirectional"))
    )
    (net (code "139") (name "unconnected-(U5A-PC15-OSC32_OUT(PC15)-Pad4)") (class "Default")
      (node (ref "U5") (pin "4") (pinfunction "PC15-OSC32_OUT(PC15)_4") (pintype "bidirectional"))
    )
    (net (code "140") (name "unconnected-(U9-CTS#-Pad9)") (class "Default")
      (node (ref "U9") (pin "9") (pinfunction "CTS#_9") (pintype "passive"))
    )
    (net (code "141") (name "unconnected-(U9-DCD#-Pad13)") (class "Default")
      (node (ref "U9") (pin "13") (pinfunction "DCD#_13") (pintype "passive"))
    )
    (net (code "142") (name "unconnected-(U9-DSR#-Pad10)") (class "Default")
      (node (ref "U9") (pin "10") (pinfunction "DSR#_10") (pintype "passive"))
    )
    (net (code "143") (name "unconnected-(U9-DTR#-Pad12)") (class "Default")
      (node (ref "U9") (pin "12") (pinfunction "DTR#_12") (pintype "passive"))
    )
    (net (code "144") (name "unconnected-(U9-R232-Pad15)") (class "Default")
      (node (ref "U9") (pin "15") (pinfunction "R232_15") (pintype "passive"))
    )
    (net (code "145") (name "unconnected-(U9-RI#-Pad14)") (class "Default")
      (node (ref "U9") (pin "14") (pinfunction "RI#_14") (pintype "passive"))
    )
    (net (code "146") (name "unconnected-(U9-RTS#-Pad11)") (class "Default")
      (node (ref "U9") (pin "11") (pinfunction "RTS#_11") (pintype "passive"))
    )
    (net (code "147") (name "unconnected-(U10-n.c.-Pad5)") (class "Default")
      (node (ref "U10") (pin "5") (pinfunction "n.c._5") (pintype "passive"))
    )
    (net (code "148") (name "unconnected-(USB_USART1-ID-Pad4)") (class "Default")
      (node (ref "USB_USART1") (pin "4") (pinfunction "ID_4") (pintype "passive"))
    )
  )
)
